# UI.net
KiCad netlist of a schematic drawn in Altium Designer
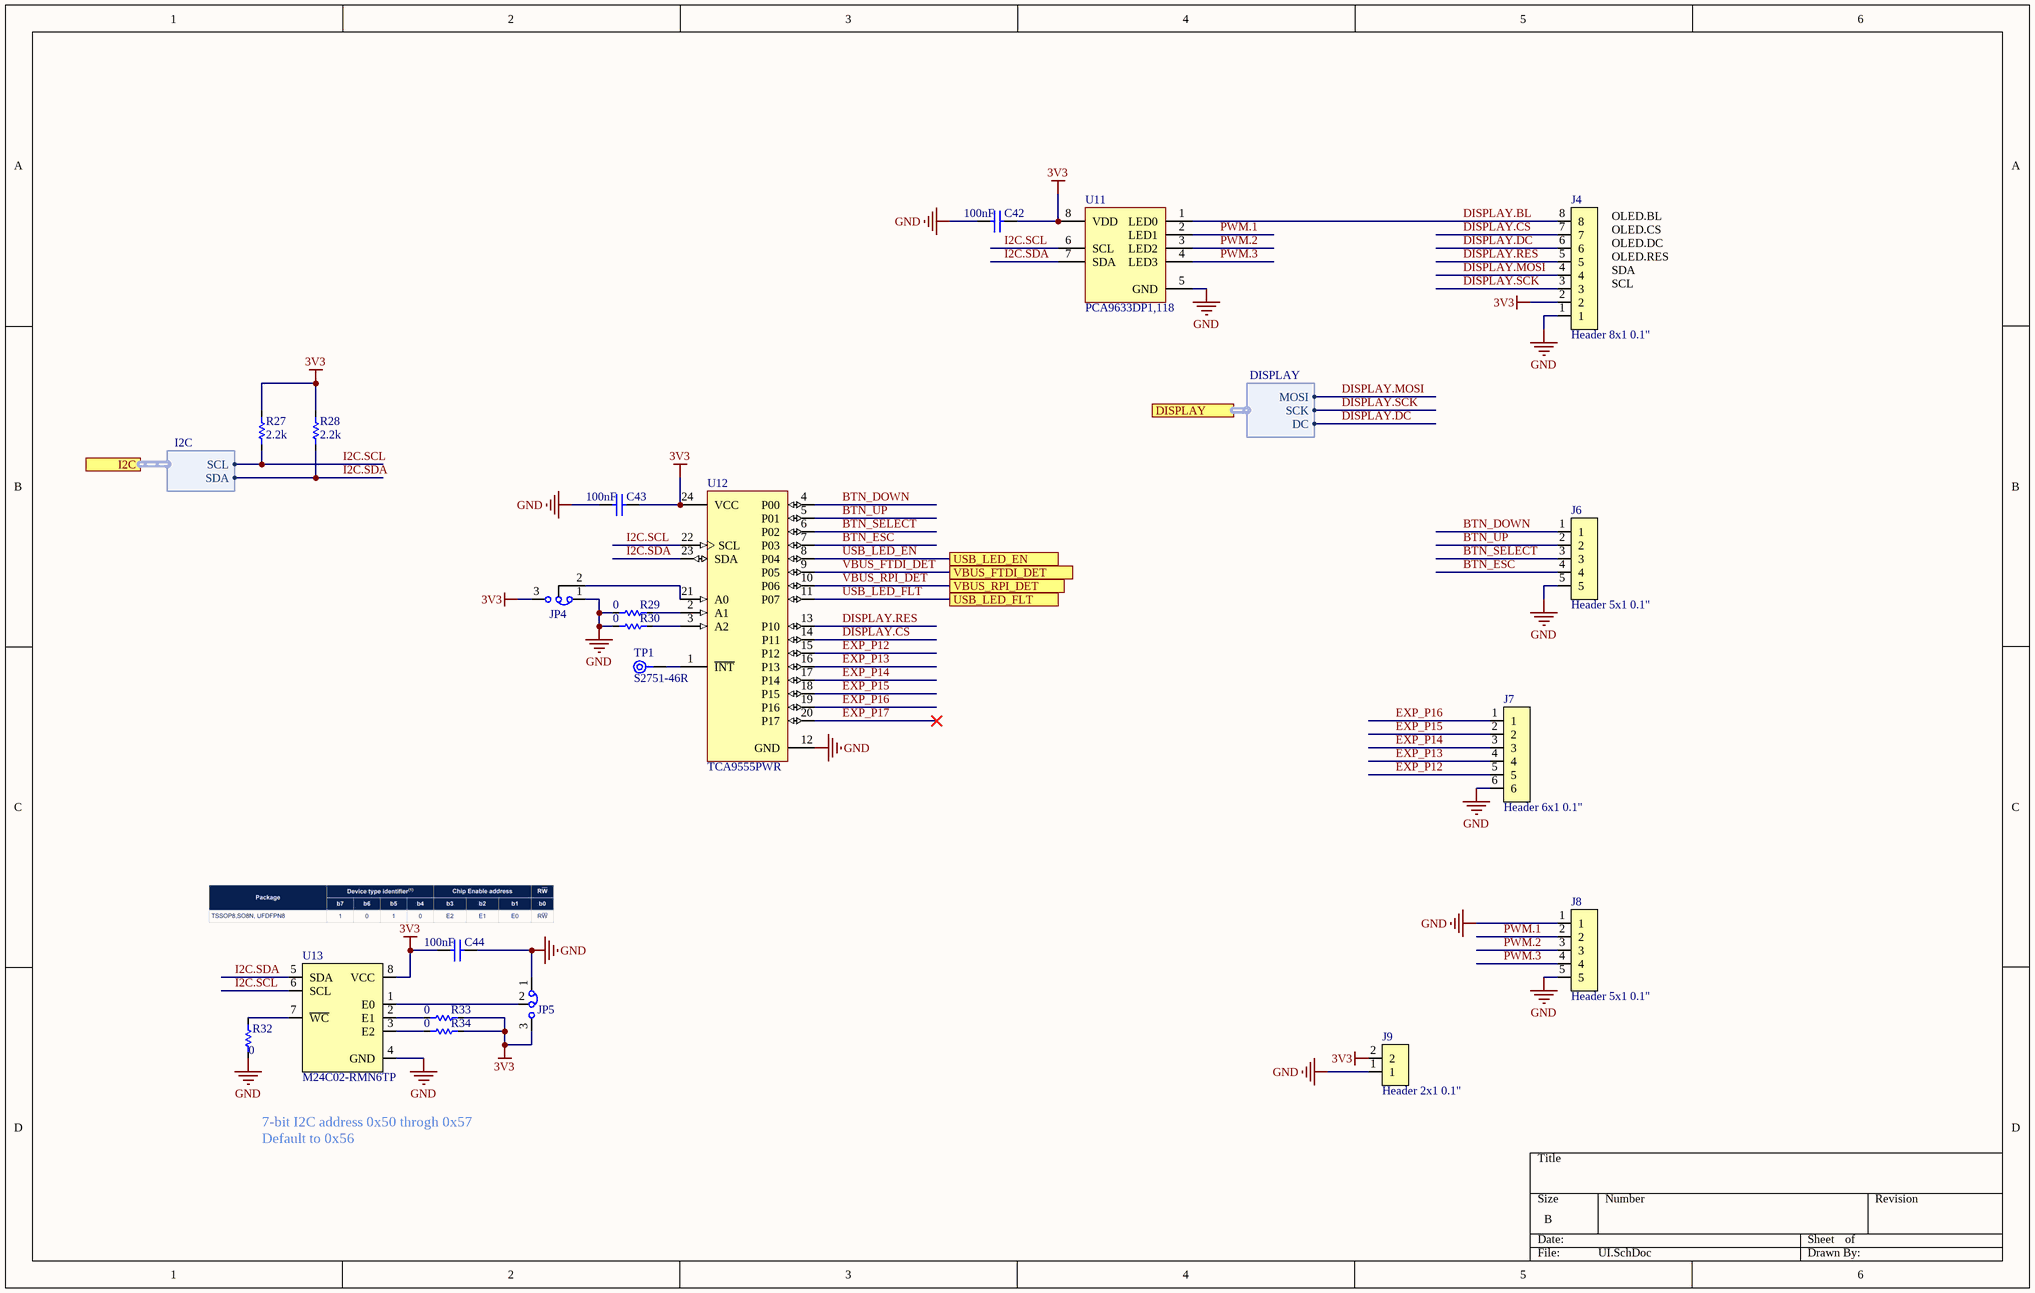
[diagram p0: UI.SchDoc]

(export (version "E")
  (design (tool "Eeschema 10.0.6"))
  (components
    (comp (ref "C42")
      (value "100nF")
      (footprint "CAPC1608X10N_0603_MED")
      (fields (field (name "Comment") "CC0603KRX7R0BB104"))
      (libsource (lib "Equus Computer Systems") (part "CAP-NP-2"))
    )
    (comp (ref "C43")
      (value "100nF")
      (footprint "CAPC1608X10N_0603_MED")
      (fields (field (name "Comment") "CC0603KRX7R0BB104"))
      (libsource (lib "Equus Computer Systems") (part "CAP-NP-2"))
    )
    (comp (ref "C44")
      (value "100nF")
      (footprint "CAPC1608X10N_0603_MED")
      (fields (field (name "Comment") "CC0603KRX7R0BB104"))
      (libsource (lib "Equus Computer Systems") (part "CAP-NP-2"))
    )
    (comp (ref "J4")
      (value "Header 8x1 0.1\"")
      (footprint "HEADER 8x1 0.1\"")
      (description "Conn Header Vert 8POS 2.54MM")
      (libsource (lib "Equus Computer Systems") (part "HEADER-8x1"))
    )
    (comp (ref "J6")
      (value "Header 5x1 0.1\"")
      (footprint "HEADER 5x1 0.1\"")
      (description "Conn Header Vert 5POS 2.54MM")
      (libsource (lib "Equus Computer Systems") (part "HEADER-5x1"))
    )
    (comp (ref "J7")
      (value "Header 6x1 0.1\"")
      (footprint "Copy of HEADER 7x1 0.1\"")
      (description "Conn Header Vert 6POS 2.54MM")
      (libsource (lib "Equus Computer Systems") (part "HEADER-6x1"))
    )
    (comp (ref "J8")
      (value "Header 5x1 0.1\"")
      (footprint "HEADER 5x1 0.1\"")
      (description "Conn Header Vert 5POS 2.54MM")
      (libsource (lib "Equus Computer Systems") (part "HEADER-5x1"))
    )
    (comp (ref "J9")
      (value "Header 2x1 0.1\"")
      (footprint "FP-M20-9990245-MFG")
      (description "Conn Header Vert 2POS 2.54MM")
      (libsource (lib "Equus Computer Systems") (part "HEADER-2x1"))
    )
    (comp (ref "JP4")
      (value "Jumper 3 x 1 Bridge 1-2 Solder Bridge")
      (footprint "Jumper 3 Solder Bridge 1-2 0603")
      (description "0603 Solder Bridge Jumper Surface Mount")
      (fields (field (name "TOLERANCE") "1%"))
      (libsource (lib "") (part "Jumper 3 Bridge 12_1"))
    )
    (comp (ref "JP5")
      (value "Jumper 3 x 1 Bridge 1-2 Solder Bridge")
      (footprint "Jumper 3 Solder Bridge 1-2 0603")
      (description "0603 Solder Bridge Jumper Surface Mount")
      (fields (field (name "TOLERANCE") "1%"))
      (libsource (lib "Equus Computer Systems") (part "Jumper 3 Bridge 12"))
    )
    (comp (ref "R27")
      (value "2.2k")
      (footprint "RESC1608X06N_0603_MED")
      (fields
        (field (name "TOLERANCE") "1%")
        (field (name "POWER") "100mW")
        (field (name "Comment") "RC0603FR-072K2L")
      )
      (libsource (lib "Equus Computer Systems") (part "RES-2"))
    )
    (comp (ref "R28")
      (value "2.2k")
      (footprint "RESC1608X06N_0603_MED")
      (fields
        (field (name "TOLERANCE") "1%")
        (field (name "POWER") "100mW")
        (field (name "Comment") "RC0603FR-072K2L")
      )
      (libsource (lib "Equus Computer Systems") (part "RES-2"))
    )
    (comp (ref "R29")
      (value "0")
      (footprint "RESC1608X06N_0603_MED")
      (description "RC Series 0603 0.1 W 0 Ohm Jumper Surface Mount Thick Film Chip Resistor")
      (fields (field (name "POWER") "100mW") (field (name "TOLERANCE") "1%"))
      (libsource (lib "Equus Computer Systems") (part "RES-2"))
    )
    (comp (ref "R30")
      (value "0")
      (footprint "RESC1608X06N_0603_MED")
      (description "RC Series 0603 0.1 W 0 Ohm Jumper Surface Mount Thick Film Chip Resistor")
      (fields (field (name "POWER") "100mW") (field (name "TOLERANCE") "1%"))
      (libsource (lib "Equus Computer Systems") (part "RES-2"))
    )
    (comp (ref "R32")
      (value "0")
      (footprint "RESC1608X06N_0603_MED")
      (description "RC Series 0603 0.1 W 0 Ohm Jumper Surface Mount Thick Film Chip Resistor")
      (fields (field (name "POWER") "100mW") (field (name "TOLERANCE") "1%"))
      (libsource (lib "Equus Computer Systems") (part "RES-2"))
    )
    (comp (ref "R33")
      (value "0")
      (footprint "RESC1608X06N_0603_MED")
      (description "RC Series 0603 0.1 W 0 Ohm Jumper Surface Mount Thick Film Chip Resistor")
      (fields (field (name "POWER") "100mW") (field (name "TOLERANCE") "1%"))
      (libsource (lib "Equus Computer Systems") (part "RES-2"))
    )
    (comp (ref "R34")
      (value "0")
      (footprint "RESC1608X06N_0603_MED")
      (description "RC Series 0603 0.1 W 0 Ohm Jumper Surface Mount Thick Film Chip Resistor")
      (fields (field (name "POWER") "100mW") (field (name "TOLERANCE") "1%"))
      (libsource (lib "Equus Computer Systems") (part "RES-2"))
    )
    (comp (ref "TP1")
      (value "S2751-46R")
      (footprint "S2751-46R")
      (description "Test Point")
      (libsource (lib "Equus Computer Systems") (part "Test-Point-BOM"))
    )
    (comp (ref "U11")
      (value "PCA9633DP1,118")
      (footprint "NXP-TSSOP-8_M")
      (description "PCA9633 Series 25 mA 5.5 V 1 MHz SMT 8-bit I2C-Bus LED Driver - TSSOP-8")
      (libsource (lib "Equus Computer Systems") (part "NXP-PCA9633-8"))
    )
    (comp (ref "U12")
      (value "TCA9555PWR")
      (footprint "PW0024A_M")
      (description "16-bit 1.65- to 5.5-V I2C/SMBus I/O expander with interrupt, weak pull-up & config registers")
      (libsource (lib "Equus Computer Systems") (part "TCA9555PWR"))
    )
    (comp (ref "U13")
      (value "M24C02-RMN6TP")
      (footprint "M24C02-RMN6TP-SO8N-IPC_B")
      (description "M24C02 Series 2 Kb (256 x 8) 1.8 V SMT Serial I²C Bus EEPROM - SOIC-8")
      (libsource (lib "Equus Computer Systems") (part "M24C02-RMN6TP"))
    )
  )
  (nets
    (net (code "3") (name "/BTN_DOWN") (class "Default")
      (node (ref "J6") (pin "1") (pinfunction "1_1") (pintype "passive"))
      (node (ref "U12") (pin "4") (pinfunction "P00_4") (pintype "bidirectional"))
    )
    (net (code "4") (name "/BTN_ESC") (class "Default")
      (node (ref "J6") (pin "4") (pinfunction "4_4") (pintype "passive"))
      (node (ref "U12") (pin "7") (pinfunction "P03_7") (pintype "bidirectional"))
    )
    (net (code "5") (name "/BTN_SELECT") (class "Default")
      (node (ref "J6") (pin "3") (pinfunction "3_3") (pintype "passive"))
      (node (ref "U12") (pin "6") (pinfunction "P02_6") (pintype "bidirectional"))
    )
    (net (code "6") (name "/BTN_UP") (class "Default")
      (node (ref "J6") (pin "2") (pinfunction "2_2") (pintype "passive"))
      (node (ref "U12") (pin "5") (pinfunction "P01_5") (pintype "bidirectional"))
    )
    (net (code "7") (name "/DISPLAY.BL") (class "Default")
      (node (ref "J4") (pin "8") (pinfunction "8_8") (pintype "passive"))
      (node (ref "U11") (pin "1") (pinfunction "LED0_1") (pintype "passive"))
    )
    (net (code "8") (name "/DISPLAY.CS") (class "Default")
      (node (ref "J4") (pin "7") (pinfunction "7_7") (pintype "passive"))
      (node (ref "U12") (pin "14") (pinfunction "P11_14") (pintype "bidirectional"))
    )
    (net (code "9") (name "/DISPLAY.DC") (class "Default")
      (node (ref "J4") (pin "6") (pinfunction "6_6") (pintype "passive"))
    )
    (net (code "10") (name "/DISPLAY.MOSI") (class "Default")
      (node (ref "J4") (pin "4") (pinfunction "4_4") (pintype "passive"))
    )
    (net (code "11") (name "/DISPLAY.RES") (class "Default")
      (node (ref "J4") (pin "5") (pinfunction "5_5") (pintype "passive"))
      (node (ref "U12") (pin "13") (pinfunction "P10_13") (pintype "bidirectional"))
    )
    (net (code "12") (name "/DISPLAY.SCK") (class "Default")
      (node (ref "J4") (pin "3") (pinfunction "3_3") (pintype "passive"))
    )
    (net (code "13") (name "/EXP_P12") (class "Default")
      (node (ref "J7") (pin "5") (pinfunction "5_5") (pintype "passive"))
      (node (ref "U12") (pin "15") (pinfunction "P12_15") (pintype "bidirectional"))
    )
    (net (code "14") (name "/EXP_P13") (class "Default")
      (node (ref "J7") (pin "4") (pinfunction "4_4") (pintype "passive"))
      (node (ref "U12") (pin "16") (pinfunction "P13_16") (pintype "bidirectional"))
    )
    (net (code "15") (name "/EXP_P14") (class "Default")
      (node (ref "J7") (pin "3") (pinfunction "3_3") (pintype "passive"))
      (node (ref "U12") (pin "17") (pinfunction "P14_17") (pintype "bidirectional"))
    )
    (net (code "16") (name "/EXP_P15") (class "Default")
      (node (ref "J7") (pin "2") (pinfunction "2_2") (pintype "passive"))
      (node (ref "U12") (pin "18") (pinfunction "P15_18") (pintype "bidirectional"))
    )
    (net (code "17") (name "/EXP_P16") (class "Default")
      (node (ref "J7") (pin "1") (pinfunction "1_1") (pintype "passive"))
      (node (ref "U12") (pin "19") (pinfunction "P16_19") (pintype "bidirectional"))
    )
    (net (code "18") (name "/EXP_P17") (class "Default")
      (node (ref "U12") (pin "20") (pinfunction "P17_20") (pintype "bidirectional+no_connect"))
    )
    (net (code "19") (name "/I2C.SCL") (class "Default")
      (node (ref "R27") (pin "1") (pinfunction "1_1") (pintype "passive"))
      (node (ref "U11") (pin "6") (pinfunction "SCL_6") (pintype "passive"))
      (node (ref "U12") (pin "22") (pinfunction "SCL_22") (pintype "input"))
      (node (ref "U13") (pin "6") (pinfunction "SCL_6") (pintype "passive"))
    )
    (net (code "20") (name "/I2C.SDA") (class "Default")
      (node (ref "R28") (pin "1") (pinfunction "1_1") (pintype "passive"))
      (node (ref "U11") (pin "7") (pinfunction "SDA_7") (pintype "passive"))
      (node (ref "U12") (pin "23") (pinfunction "SDA_23") (pintype "bidirectional"))
      (node (ref "U13") (pin "5") (pinfunction "SDA_5") (pintype "passive"))
    )
    (net (code "21") (name "/PWM.1") (class "Default")
      (node (ref "J8") (pin "2") (pinfunction "2_2") (pintype "passive"))
      (node (ref "U11") (pin "2") (pinfunction "LED1_2") (pintype "passive"))
    )
    (net (code "22") (name "/PWM.2") (class "Default")
      (node (ref "J8") (pin "3") (pinfunction "3_3") (pintype "passive"))
      (node (ref "U11") (pin "3") (pinfunction "LED2_3") (pintype "passive"))
    )
    (net (code "23") (name "/PWM.3") (class "Default")
      (node (ref "J8") (pin "4") (pinfunction "4_4") (pintype "passive"))
      (node (ref "U11") (pin "4") (pinfunction "LED3_4") (pintype "passive"))
    )
    (net (code "24") (name "/USB_LED_EN") (class "Default")
      (node (ref "U12") (pin "8") (pinfunction "P04_8") (pintype "bidirectional"))
    )
    (net (code "25") (name "/USB_LED_FLT") (class "Default")
      (node (ref "U12") (pin "11") (pinfunction "P07_11") (pintype "bidirectional"))
    )
    (net (code "26") (name "/VBUS_FTDI_DET") (class "Default")
      (node (ref "U12") (pin "9") (pinfunction "P05_9") (pintype "bidirectional"))
    )
    (net (code "27") (name "/VBUS_RPI_DET") (class "Default")
      (node (ref "U12") (pin "10") (pinfunction "P06_10") (pintype "bidirectional"))
    )
    (net (code "30") (name "3V3") (class "Default")
      (node (ref "C42") (pin "2") (pinfunction "2_2") (pintype "passive"))
      (node (ref "C43") (pin "2") (pinfunction "2_2") (pintype "passive"))
      (node (ref "C44") (pin "1") (pinfunction "1_1") (pintype "passive"))
      (node (ref "J4") (pin "2") (pinfunction "2_2") (pintype "passive"))
      (node (ref "J9") (pin "2") (pinfunction "2_2") (pintype "passive"))
      (node (ref "JP4") (pin "3") (pinfunction "3_3") (pintype "passive"))
      (node (ref "JP5") (pin "3") (pinfunction "3_3") (pintype "passive"))
      (node (ref "R27") (pin "2") (pinfunction "2_2") (pintype "passive"))
      (node (ref "R28") (pin "2") (pinfunction "2_2") (pintype "passive"))
      (node (ref "R33") (pin "1") (pinfunction "1_1") (pintype "passive"))
      (node (ref "R34") (pin "1") (pinfunction "1_1") (pintype "passive"))
      (node (ref "U11") (pin "8") (pinfunction "VDD_8") (pintype "power_in"))
      (node (ref "U12") (pin "24") (pinfunction "VCC_24") (pintype "power_in"))
      (node (ref "U13") (pin "8") (pinfunction "VCC_8") (pintype "power_in"))
    )
    (net (code "31") (name "GND") (class "Default")
      (node (ref "C42") (pin "1") (pinfunction "1_1") (pintype "passive"))
      (node (ref "C43") (pin "1") (pinfunction "1_1") (pintype "passive"))
      (node (ref "C44") (pin "2") (pinfunction "2_2") (pintype "passive"))
      (node (ref "J4") (pin "1") (pinfunction "1_1") (pintype "passive"))
      (node (ref "J6") (pin "5") (pinfunction "5_5") (pintype "passive"))
      (node (ref "J7") (pin "6") (pinfunction "6_6") (pintype "passive"))
      (node (ref "J8") (pin "1") (pinfunction "1_1") (pintype "passive"))
      (node (ref "J8") (pin "5") (pinfunction "5_5") (pintype "passive"))
      (node (ref "J9") (pin "1") (pinfunction "1_1") (pintype "passive"))
      (node (ref "JP4") (pin "1") (pinfunction "1_1") (pintype "passive"))
      (node (ref "JP5") (pin "1") (pinfunction "1_1") (pintype "passive"))
      (node (ref "R29") (pin "2") (pinfunction "2_2") (pintype "passive"))
      (node (ref "R30") (pin "2") (pinfunction "2_2") (pintype "passive"))
      (node (ref "R32") (pin "2") (pinfunction "2_2") (pintype "passive"))
      (node (ref "U11") (pin "5") (pinfunction "GND_5") (pintype "passive"))
      (node (ref "U12") (pin "12") (pinfunction "GND_12") (pintype "power_in"))
      (node (ref "U13") (pin "4") (pinfunction "GND_4") (pintype "power_in"))
    )
    (net (code "32") (name "Net-(U12-A0)") (class "Default")
      (node (ref "JP4") (pin "2") (pinfunction "2_2") (pintype "passive"))
      (node (ref "U12") (pin "21") (pinfunction "A0_21") (pintype "input"))
    )
    (net (code "33") (name "Net-(U12-A1)") (class "Default")
      (node (ref "R29") (pin "1") (pinfunction "1_1") (pintype "passive"))
      (node (ref "U12") (pin "2") (pinfunction "A1_2") (pintype "input"))
    )
    (net (code "34") (name "Net-(U12-A2)") (class "Default")
      (node (ref "R30") (pin "1") (pinfunction "1_1") (pintype "passive"))
      (node (ref "U12") (pin "3") (pinfunction "A2_3") (pintype "input"))
    )
    (net (code "35") (name "Net-(U12-~{INT})") (class "Default")
      (node (ref "TP1") (pin "1") (pinfunction "1_1") (pintype "passive"))
      (node (ref "U12") (pin "1") (pinfunction "~{INT}_1") (pintype "open_collector"))
    )
    (net (code "36") (name "Net-(U13-E0)") (class "Default")
      (node (ref "JP5") (pin "2") (pinfunction "2_2") (pintype "passive"))
      (node (ref "U13") (pin "1") (pinfunction "E0_1") (pintype "passive"))
    )
    (net (code "37") (name "Net-(U13-E1)") (class "Default")
      (node (ref "R33") (pin "2") (pinfunction "2_2") (pintype "passive"))
      (node (ref "U13") (pin "2") (pinfunction "E1_2") (pintype "passive"))
    )
    (net (code "38") (name "Net-(U13-E2)") (class "Default")
      (node (ref "R34") (pin "2") (pinfunction "2_2") (pintype "passive"))
      (node (ref "U13") (pin "3") (pinfunction "E2_3") (pintype "passive"))
    )
    (net (code "39") (name "Net-(U13-~{WC})") (class "Default")
      (node (ref "R32") (pin "1") (pinfunction "1_1") (pintype "passive"))
      (node (ref "U13") (pin "7") (pinfunction "~{WC}_7") (pintype "passive"))
    )
  )
)
